# Cegep2.net
KiCad netlist of a schematic drawn in Altium Designer
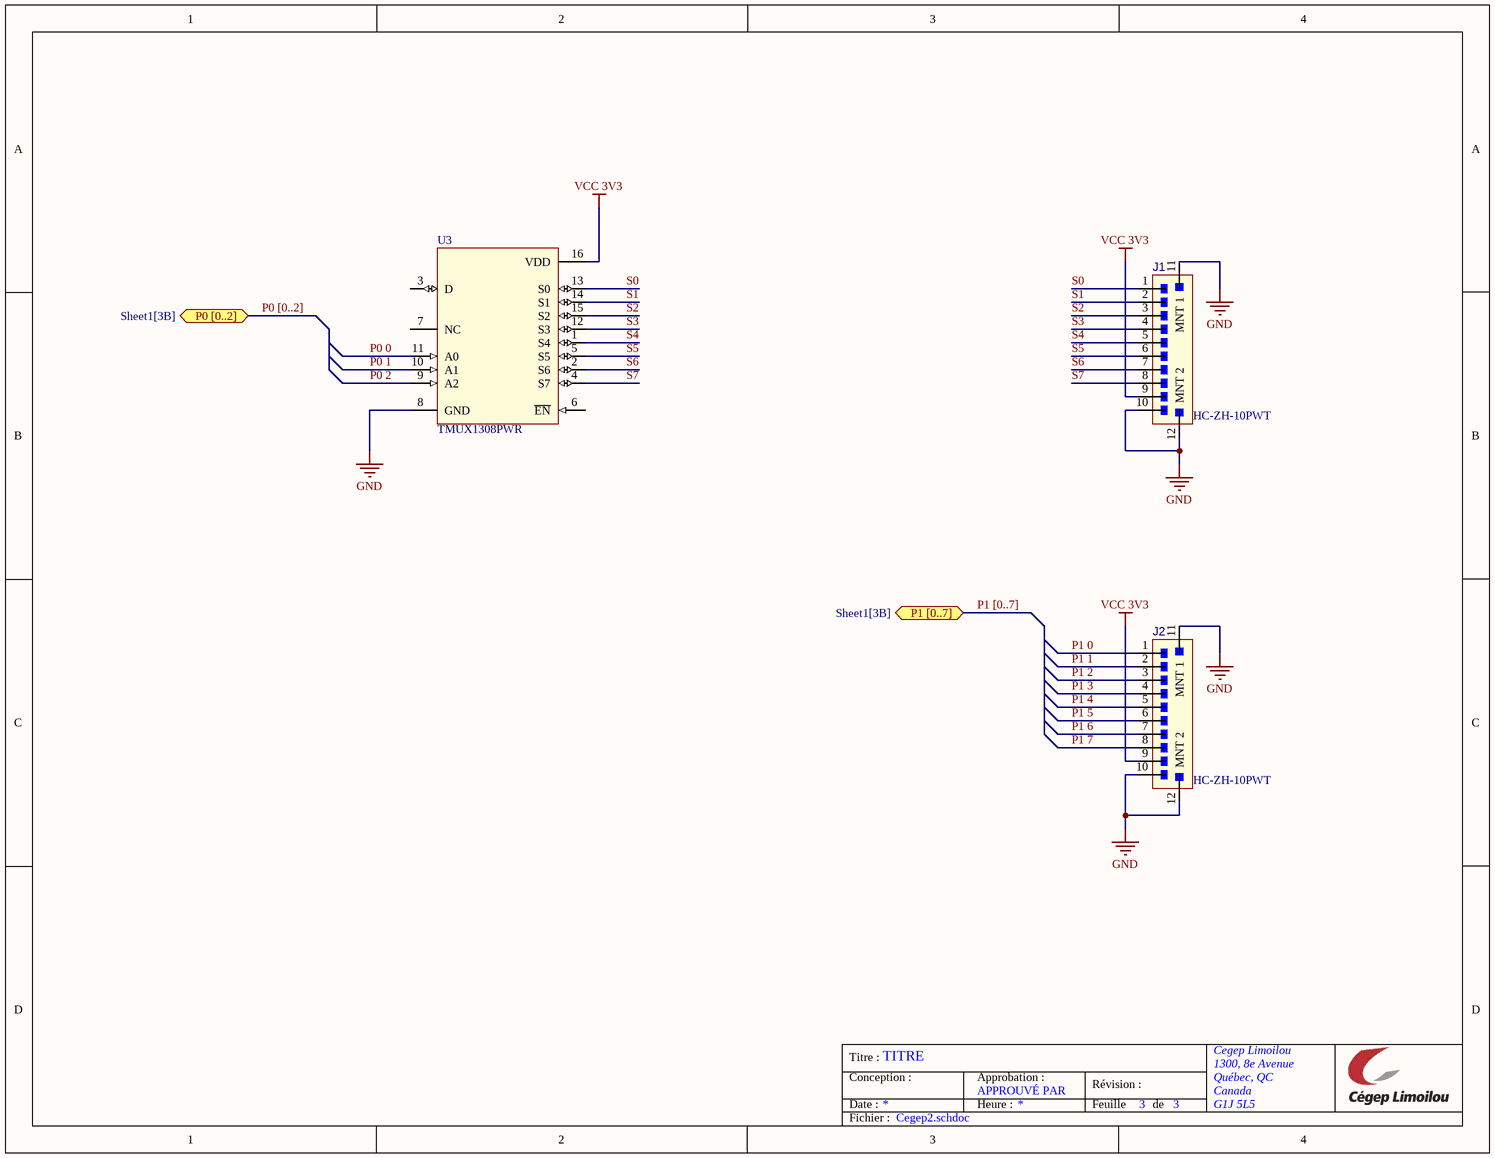
[diagram p0: Cegep2.schdoc]

(export (version "E")
  (design (tool "Eeschema 10.0.6"))
  (components
    (comp (ref "J1")
      (value "HC-ZH-10PWT")
      (footprint "J_S10B-ZR-SM4")
      (description "CONN wire to board SMT R/A 10POS 1.5mm")
      (libsource (lib "TEP-AltiumLib-Connectors") (part "CONN-1MM5-01X10-S10B-H-SMT"))
    )
    (comp (ref "J2")
      (value "HC-ZH-10PWT")
      (footprint "J_S10B-ZR-SM4")
      (description "CONN wire to board SMT R/A 10POS 1.5mm")
      (libsource (lib "TEP-AltiumLib-Connectors") (part "CONN-1MM5-01X10-S10B-H-SMT"))
    )
    (comp (ref "U3")
      (value "TMUX1308PWR")
      (footprint "U_TSSOP65P500X450-16")
      (description "IC MUX 8:1 195OHM 16TSSOP")
      (libsource (lib "TEP-AltiumLib-ICs") (part "U_TMUX1308PWR"))
    )
  )
  (nets
    (net (code "1") (name "/P0 0") (class "Default")
      (node (ref "U3") (pin "11") (pinfunction "A0_11") (pintype "input"))
    )
    (net (code "2") (name "/P0 1") (class "Default")
      (node (ref "U3") (pin "10") (pinfunction "A1_10") (pintype "input"))
    )
    (net (code "3") (name "/P0 2") (class "Default")
      (node (ref "U3") (pin "9") (pinfunction "A2_9") (pintype "input"))
    )
    (net (code "4") (name "/P1 0") (class "Default")
      (node (ref "J2") (pin "1") (pinfunction "1_1") (pintype "passive"))
    )
    (net (code "5") (name "/P1 1") (class "Default")
      (node (ref "J2") (pin "2") (pinfunction "2_2") (pintype "passive"))
    )
    (net (code "6") (name "/P1 2") (class "Default")
      (node (ref "J2") (pin "3") (pinfunction "3_3") (pintype "passive"))
    )
    (net (code "7") (name "/P1 3") (class "Default")
      (node (ref "J2") (pin "4") (pinfunction "4_4") (pintype "passive"))
    )
    (net (code "8") (name "/P1 4") (class "Default")
      (node (ref "J2") (pin "5") (pinfunction "5_5") (pintype "passive"))
    )
    (net (code "9") (name "/P1 5") (class "Default")
      (node (ref "J2") (pin "6") (pinfunction "6_6") (pintype "passive"))
    )
    (net (code "10") (name "/P1 6") (class "Default")
      (node (ref "J2") (pin "7") (pinfunction "7_7") (pintype "passive"))
    )
    (net (code "11") (name "/P1 7") (class "Default")
      (node (ref "J2") (pin "8") (pinfunction "8_8") (pintype "passive"))
    )
    (net (code "12") (name "/S0") (class "Default")
      (node (ref "J1") (pin "1") (pinfunction "1_1") (pintype "passive"))
      (node (ref "U3") (pin "13") (pinfunction "S0_13") (pintype "bidirectional"))
    )
    (net (code "13") (name "/S1") (class "Default")
      (node (ref "J1") (pin "2") (pinfunction "2_2") (pintype "passive"))
      (node (ref "U3") (pin "14") (pinfunction "S1_14") (pintype "bidirectional"))
    )
    (net (code "14") (name "/S2") (class "Default")
      (node (ref "J1") (pin "3") (pinfunction "3_3") (pintype "passive"))
      (node (ref "U3") (pin "15") (pinfunction "S2_15") (pintype "bidirectional"))
    )
    (net (code "15") (name "/S3") (class "Default")
      (node (ref "J1") (pin "4") (pinfunction "4_4") (pintype "passive"))
      (node (ref "U3") (pin "12") (pinfunction "S3_12") (pintype "bidirectional"))
    )
    (net (code "16") (name "/S4") (class "Default")
      (node (ref "J1") (pin "5") (pinfunction "5_5") (pintype "passive"))
      (node (ref "U3") (pin "1") (pinfunction "S4_1") (pintype "bidirectional"))
    )
    (net (code "17") (name "/S5") (class "Default")
      (node (ref "J1") (pin "6") (pinfunction "6_6") (pintype "passive"))
      (node (ref "U3") (pin "5") (pinfunction "S5_5") (pintype "bidirectional"))
    )
    (net (code "18") (name "/S6") (class "Default")
      (node (ref "J1") (pin "7") (pinfunction "7_7") (pintype "passive"))
      (node (ref "U3") (pin "2") (pinfunction "S6_2") (pintype "bidirectional"))
    )
    (net (code "19") (name "/S7") (class "Default")
      (node (ref "J1") (pin "8") (pinfunction "8_8") (pintype "passive"))
      (node (ref "U3") (pin "4") (pinfunction "S7_4") (pintype "bidirectional"))
    )
    (net (code "22") (name "GND") (class "Default")
      (node (ref "J1") (pin "10") (pinfunction "10_10") (pintype "passive"))
      (node (ref "J1") (pin "11") (pinfunction "MNT_1_11") (pintype "passive"))
      (node (ref "J1") (pin "12") (pinfunction "MNT_2_12") (pintype "passive"))
      (node (ref "J2") (pin "10") (pinfunction "10_10") (pintype "passive"))
      (node (ref "J2") (pin "11") (pinfunction "MNT_1_11") (pintype "passive"))
      (node (ref "J2") (pin "12") (pinfunction "MNT_2_12") (pintype "passive"))
      (node (ref "U3") (pin "8") (pinfunction "GND_8") (pintype "power_in"))
    )
    (net (code "23") (name "VCC 3V3") (class "Default")
      (node (ref "J1") (pin "9") (pinfunction "9_9") (pintype "passive"))
      (node (ref "J2") (pin "9") (pinfunction "9_9") (pintype "passive"))
      (node (ref "U3") (pin "16") (pinfunction "VDD_16") (pintype "power_in"))
    )
    (net (code "24") (name "unconnected-(U3-D-Pad3)") (class "Default")
      (node (ref "U3") (pin "3") (pinfunction "D_3") (pintype "bidirectional"))
    )
    (net (code "25") (name "unconnected-(U3-NC-Pad7)") (class "Default")
      (node (ref "U3") (pin "7") (pinfunction "NC_7") (pintype "passive"))
    )
    (net (code "26") (name "unconnected-(U3-~{EN}-Pad6)") (class "Default")
      (node (ref "U3") (pin "6") (pinfunction "~{EN}_6") (pintype "input"))
    )
  )
)
